# ESP.net
KiCad netlist of a schematic drawn in EAGLE
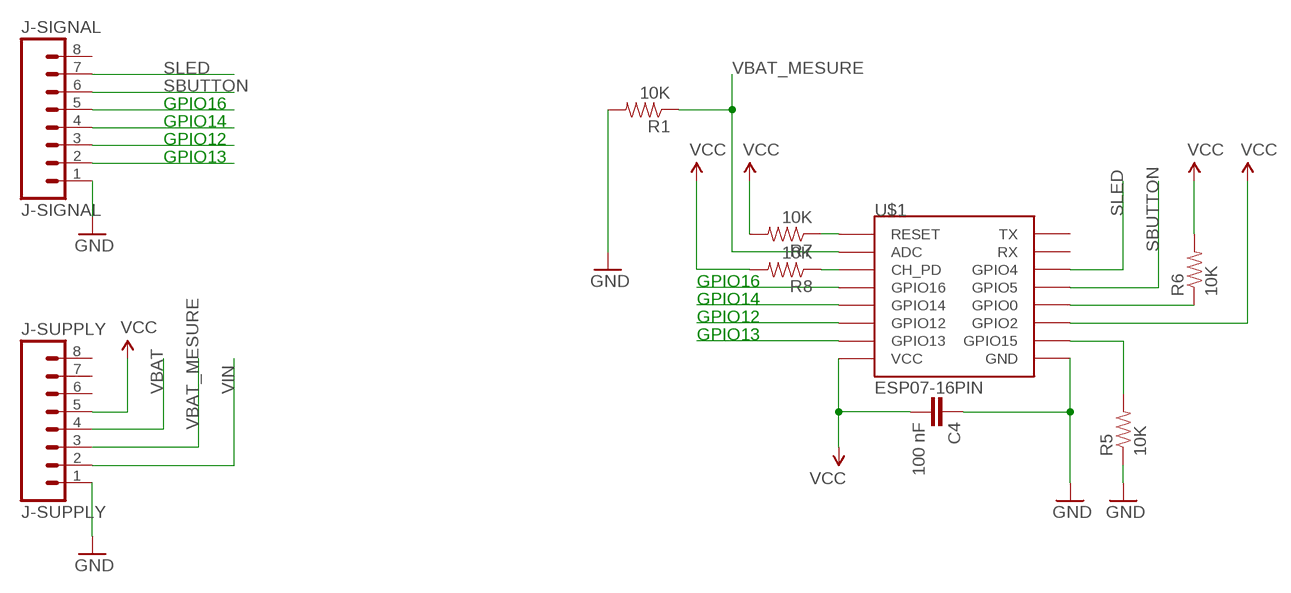
[diagram p0: schematic, sheet 1]

(export (version "E")
  (design (tool "Eeschema 10.0.6"))
  (components
    (comp (ref "C4")
      (value "100 nF")
      (footprint "eagle-import:1206")
      (libsource (lib "eagle-import") (part "CAP1206"))
    )
    (comp (ref "J-SIGNAL")
      (value "J-SIGNAL")
      (footprint "eagle-import:1X08_ROUND")
      (libsource (lib "eagle-import") (part "M08"))
    )
    (comp (ref "J-SUPPLY")
      (value "J-SUPPLY")
      (footprint "eagle-import:1X08_ROUND")
      (libsource (lib "eagle-import") (part "M08"))
    )
    (comp (ref "R1")
      (value "10K")
      (footprint "eagle-import:0805")
      (libsource (lib "eagle-import") (part "RESISTOR0805-RES"))
    )
    (comp (ref "R5")
      (value "10K")
      (footprint "eagle-import:0805")
      (libsource (lib "eagle-import") (part "RESISTOR0805-RES"))
    )
    (comp (ref "R6")
      (value "10K")
      (footprint "eagle-import:0805")
      (libsource (lib "eagle-import") (part "RESISTOR0805-RES"))
    )
    (comp (ref "R7")
      (value "10K")
      (footprint "eagle-import:0805")
      (libsource (lib "eagle-import") (part "RESISTOR0805-RES"))
    )
    (comp (ref "R8")
      (value "10K")
      (footprint "eagle-import:0805")
      (libsource (lib "eagle-import") (part "RESISTOR0805-RES"))
    )
    (comp (ref "U$1")
      (value "ESP07-16PIN")
      (footprint "eagle-import:ESP07-16PIN")
      (libsource (lib "eagle-import") (part "ESP07-16PIN"))
    )
  )
  (nets
    (net (code "1") (name "/GPIO12") (class "Default")
      (node (ref "J-SIGNAL") (pin "3") (pinfunction "3_3") (pintype "passive"))
      (node (ref "U$1") (pin "GPIO12") (pinfunction "GPIO12_GPIO12") (pintype "bidirectional"))
    )
    (net (code "2") (name "/GPIO13") (class "Default")
      (node (ref "J-SIGNAL") (pin "2") (pinfunction "2_2") (pintype "passive"))
      (node (ref "U$1") (pin "GPIO13") (pinfunction "GPIO13_GPIO13") (pintype "bidirectional"))
    )
    (net (code "3") (name "/GPIO14") (class "Default")
      (node (ref "J-SIGNAL") (pin "4") (pinfunction "4_4") (pintype "passive"))
      (node (ref "U$1") (pin "GPIO14") (pinfunction "GPIO14_GPIO14") (pintype "bidirectional"))
    )
    (net (code "4") (name "/GPIO16") (class "Default")
      (node (ref "J-SIGNAL") (pin "5") (pinfunction "5_5") (pintype "passive"))
      (node (ref "U$1") (pin "GPIO16") (pinfunction "GPIO16_GPIO16") (pintype "bidirectional"))
    )
    (net (code "5") (name "/SBUTTON") (class "Default")
      (node (ref "J-SIGNAL") (pin "6") (pinfunction "6_6") (pintype "passive"))
      (node (ref "U$1") (pin "GPIO5") (pinfunction "GPIO5_GPIO5") (pintype "bidirectional"))
    )
    (net (code "6") (name "/SLED") (class "Default")
      (node (ref "J-SIGNAL") (pin "7") (pinfunction "7_7") (pintype "passive"))
      (node (ref "U$1") (pin "GPIO4") (pinfunction "GPIO4_GPIO4") (pintype "bidirectional"))
    )
    (net (code "7") (name "/VBAT") (class "Default")
      (node (ref "J-SUPPLY") (pin "4") (pinfunction "4_4") (pintype "passive"))
    )
    (net (code "8") (name "/VBAT_MESURE") (class "Default")
      (node (ref "J-SUPPLY") (pin "3") (pinfunction "3_3") (pintype "passive"))
      (node (ref "R1") (pin "1") (pinfunction "1_1") (pintype "passive"))
      (node (ref "U$1") (pin "ADC") (pinfunction "ADC_ADC") (pintype "bidirectional"))
    )
    (net (code "9") (name "/VIN") (class "Default")
      (node (ref "J-SUPPLY") (pin "2") (pinfunction "2_2") (pintype "passive"))
    )
    (net (code "10") (name "GND") (class "Default")
      (node (ref "C4") (pin "1") (pinfunction "1_1") (pintype "passive"))
      (node (ref "J-SIGNAL") (pin "1") (pinfunction "1_1") (pintype "passive"))
      (node (ref "J-SUPPLY") (pin "1") (pinfunction "1_1") (pintype "passive"))
      (node (ref "R1") (pin "2") (pinfunction "2_2") (pintype "passive"))
      (node (ref "R5") (pin "1") (pinfunction "1_1") (pintype "passive"))
      (node (ref "U$1") (pin "GND") (pinfunction "GND_GND") (pintype "bidirectional"))
    )
    (net (code "11") (name "Net-(R5-Pad2)") (class "Default")
      (node (ref "R5") (pin "2") (pinfunction "2_2") (pintype "passive"))
      (node (ref "U$1") (pin "GPIO15") (pinfunction "GPIO15_GPIO15") (pintype "bidirectional"))
    )
    (net (code "12") (name "Net-(R6-Pad1)") (class "Default")
      (node (ref "R6") (pin "1") (pinfunction "1_1") (pintype "passive"))
      (node (ref "U$1") (pin "GPIO0") (pinfunction "GPIO0_GPIO0") (pintype "bidirectional"))
    )
    (net (code "13") (name "Net-(R8-Pad1)") (class "Default")
      (node (ref "R8") (pin "1") (pinfunction "1_1") (pintype "passive"))
      (node (ref "U$1") (pin "CH_PD") (pinfunction "CH_PD_CH_PD") (pintype "bidirectional"))
    )
    (net (code "14") (name "Net-(U$1-RESET)") (class "Default")
      (node (ref "R7") (pin "1") (pinfunction "1_1") (pintype "passive"))
      (node (ref "U$1") (pin "REST") (pinfunction "RESET_REST") (pintype "bidirectional"))
    )
    (net (code "15") (name "VCC") (class "Default")
      (node (ref "C4") (pin "2") (pinfunction "2_2") (pintype "passive"))
      (node (ref "J-SUPPLY") (pin "5") (pinfunction "5_5") (pintype "passive"))
      (node (ref "R6") (pin "2") (pinfunction "2_2") (pintype "passive"))
      (node (ref "R7") (pin "2") (pinfunction "2_2") (pintype "passive"))
      (node (ref "R8") (pin "2") (pinfunction "2_2") (pintype "passive"))
      (node (ref "U$1") (pin "GPIO2") (pinfunction "GPIO2_GPIO2") (pintype "bidirectional"))
      (node (ref "U$1") (pin "VCC") (pinfunction "VCC_VCC") (pintype "bidirectional"))
    )
    (net (code "16") (name "unconnected-(J-SIGNAL-Pad8)") (class "Default")
      (node (ref "J-SIGNAL") (pin "8") (pinfunction "8_8") (pintype "passive"))
    )
    (net (code "17") (name "unconnected-(J-SUPPLY-Pad6)") (class "Default")
      (node (ref "J-SUPPLY") (pin "6") (pinfunction "6_6") (pintype "passive"))
    )
    (net (code "18") (name "unconnected-(J-SUPPLY-Pad7)") (class "Default")
      (node (ref "J-SUPPLY") (pin "7") (pinfunction "7_7") (pintype "passive"))
    )
    (net (code "19") (name "unconnected-(J-SUPPLY-Pad8)") (class "Default")
      (node (ref "J-SUPPLY") (pin "8") (pinfunction "8_8") (pintype "passive"))
    )
    (net (code "20") (name "unconnected-(U$1-PadRX)") (class "Default")
      (node (ref "U$1") (pin "RX") (pinfunction "RX_RX") (pintype "bidirectional"))
    )
    (net (code "21") (name "unconnected-(U$1-PadTX)") (class "Default")
      (node (ref "U$1") (pin "TX") (pinfunction "TX_TX") (pintype "bidirectional"))
    )
  )
)
